# MAX78630_SOC.net
KiCad netlist of a schematic drawn in Altium Designer
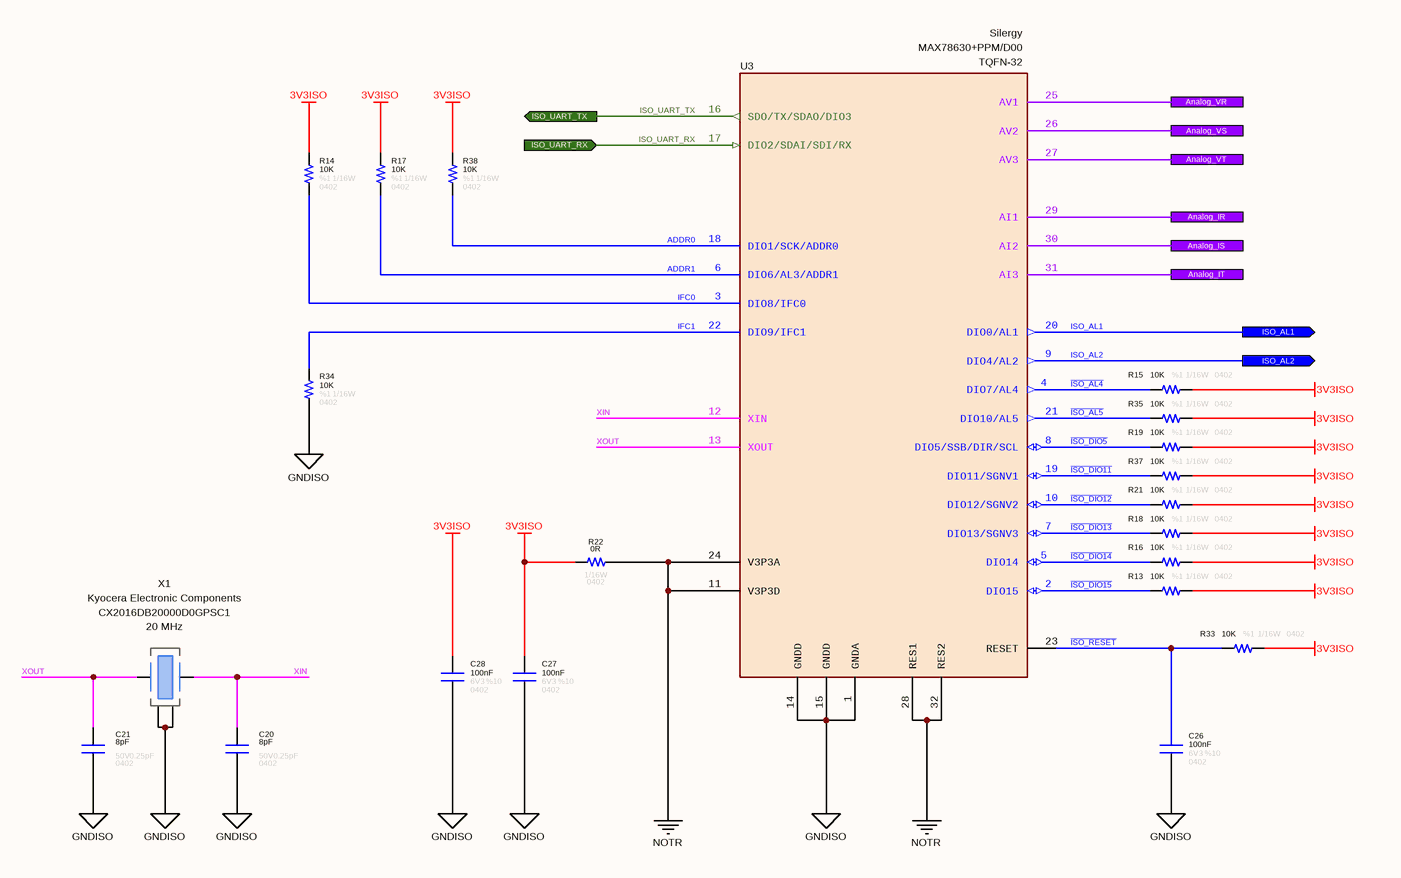
[diagram p0: MAX78630 SOC.SchDoc]

(export (version "E")
  (design (tool "Eeschema 10.0.6"))
  (components
    (comp (ref "C20")
      (value "8pF")
      (footprint "CAPACITOR_0402")
      (description "Capacitor - 8pF [0402] (Ceramic)")
      (fields
        (field (name "MANUFACTURER PART NUMBER") "04025A8R0CAT2A")
        (field (name "TOLERANCE") "0.25pF")
        (field (name "CASE") "0402")
        (field (name "VOLTAGE") "50V")
      )
      (libsource (lib "Akkoyun") (part "Capacitor - 8pF [0402-50V]"))
    )
    (comp (ref "C21")
      (value "8pF")
      (footprint "CAPACITOR_0402")
      (description "Capacitor - 8pF [0402] (Ceramic)")
      (fields
        (field (name "MANUFACTURER PART NUMBER") "04025A8R0CAT2A")
        (field (name "TOLERANCE") "0.25pF")
        (field (name "CASE") "0402")
        (field (name "VOLTAGE") "50V")
      )
      (libsource (lib "Akkoyun") (part "Capacitor - 8pF [0402-50V]"))
    )
    (comp (ref "C26")
      (value "100nF")
      (footprint "CAPACITOR_0402")
      (description "Capacitor - 100nF [0402-6V3] (Ceramic)")
      (fields
        (field (name "MANUFACTURER PART NUMBER") "04026D104KAT4A")
        (field (name "TOLERANCE") "%10")
        (field (name "VOLTAGE") "6V3")
        (field (name "CASE") "0402")
        (field (name "Comment") "Capacitor - 100nF [0402] (Ceramic)")
      )
      (libsource (lib "Akkoyun") (part "Capacitor - 100nF [0402-6V3]"))
    )
    (comp (ref "C27")
      (value "100nF")
      (footprint "CAPACITOR_0402")
      (description "Capacitor - 100nF [0402-6V3] (Ceramic)")
      (fields
        (field (name "MANUFACTURER PART NUMBER") "04026D104KAT4A")
        (field (name "TOLERANCE") "%10")
        (field (name "VOLTAGE") "6V3")
        (field (name "CASE") "0402")
        (field (name "Comment") "Capacitor - 100nF [0402] (Ceramic)")
      )
      (libsource (lib "Akkoyun") (part "Capacitor - 100nF [0402-6V3]"))
    )
    (comp (ref "C28")
      (value "100nF")
      (footprint "CAPACITOR_0402")
      (description "Capacitor - 100nF [0402-6V3] (Ceramic)")
      (fields
        (field (name "MANUFACTURER PART NUMBER") "04026D104KAT4A")
        (field (name "TOLERANCE") "%10")
        (field (name "VOLTAGE") "6V3")
        (field (name "CASE") "0402")
        (field (name "Comment") "Capacitor - 100nF [0402] (Ceramic)")
      )
      (libsource (lib "Akkoyun") (part "Capacitor - 100nF [0402-6V3]"))
    )
    (comp (ref "R13")
      (value "10K")
      (footprint "RESISTOR_0402")
      (description "Thick Film Resistors - SMD 1/16 W 10 KOhm 1%")
      (fields
        (field (name "MANUFACTURER PART NUMBER") "CRCW040210K0FKED")
        (field (name "TOLERANCE") "%1")
        (field (name "CASE") "0402")
        (field (name "POWER") "1/16W")
        (field (name "Comment") "10K - 0402 - %1 - 1/16W")
      )
      (libsource (lib "Akkoyun") (part "Resistor - 10K [0402]"))
    )
    (comp (ref "R14")
      (value "10K")
      (footprint "RESISTOR_0402")
      (description "Thick Film Resistors - SMD 1/16 W 10 KOhm 1%")
      (fields
        (field (name "MANUFACTURER PART NUMBER") "CRCW040210K0FKED")
        (field (name "TOLERANCE") "%1")
        (field (name "CASE") "0402")
        (field (name "POWER") "1/16W")
        (field (name "Comment") "10K - 0402 - %1 - 1/16W")
      )
      (libsource (lib "Akkoyun") (part "Resistor - 10K [0402]"))
    )
    (comp (ref "R15")
      (value "10K")
      (footprint "RESISTOR_0402")
      (description "Thick Film Resistors - SMD 1/16 W 10 KOhm 1%")
      (fields
        (field (name "MANUFACTURER PART NUMBER") "CRCW040210K0FKED")
        (field (name "TOLERANCE") "%1")
        (field (name "CASE") "0402")
        (field (name "POWER") "1/16W")
        (field (name "Comment") "10K - 0402 - %1 - 1/16W")
      )
      (libsource (lib "Akkoyun") (part "Resistor - 10K [0402]"))
    )
    (comp (ref "R16")
      (value "10K")
      (footprint "RESISTOR_0402")
      (description "Thick Film Resistors - SMD 1/16 W 10 KOhm 1%")
      (fields
        (field (name "MANUFACTURER PART NUMBER") "CRCW040210K0FKED")
        (field (name "TOLERANCE") "%1")
        (field (name "CASE") "0402")
        (field (name "POWER") "1/16W")
        (field (name "Comment") "10K - 0402 - %1 - 1/16W")
      )
      (libsource (lib "Akkoyun") (part "Resistor - 10K [0402]"))
    )
    (comp (ref "R17")
      (value "10K")
      (footprint "RESISTOR_0402")
      (description "Thick Film Resistors - SMD 1/16 W 10 KOhm 1%")
      (fields
        (field (name "MANUFACTURER PART NUMBER") "CRCW040210K0FKED")
        (field (name "TOLERANCE") "%1")
        (field (name "CASE") "0402")
        (field (name "POWER") "1/16W")
        (field (name "Comment") "10K - 0402 - %1 - 1/16W")
      )
      (libsource (lib "Akkoyun") (part "Resistor - 10K [0402]"))
    )
    (comp (ref "R18")
      (value "10K")
      (footprint "RESISTOR_0402")
      (description "Thick Film Resistors - SMD 1/16 W 10 KOhm 1%")
      (fields
        (field (name "MANUFACTURER PART NUMBER") "CRCW040210K0FKED")
        (field (name "TOLERANCE") "%1")
        (field (name "CASE") "0402")
        (field (name "POWER") "1/16W")
        (field (name "Comment") "10K - 0402 - %1 - 1/16W")
      )
      (libsource (lib "Akkoyun") (part "Resistor - 10K [0402]"))
    )
    (comp (ref "R19")
      (value "10K")
      (footprint "RESISTOR_0402")
      (description "Thick Film Resistors - SMD 1/16 W 10 KOhm 1%")
      (fields
        (field (name "MANUFACTURER PART NUMBER") "CRCW040210K0FKED")
        (field (name "TOLERANCE") "%1")
        (field (name "CASE") "0402")
        (field (name "POWER") "1/16W")
        (field (name "Comment") "10K - 0402 - %1 - 1/16W")
      )
      (libsource (lib "Akkoyun") (part "Resistor - 10K [0402]"))
    )
    (comp (ref "R21")
      (value "10K")
      (footprint "RESISTOR_0402")
      (description "Thick Film Resistors - SMD 1/16 W 10 KOhm 1%")
      (fields
        (field (name "MANUFACTURER PART NUMBER") "CRCW040210K0FKED")
        (field (name "TOLERANCE") "%1")
        (field (name "CASE") "0402")
        (field (name "POWER") "1/16W")
        (field (name "Comment") "10K - 0402 - %1 - 1/16W")
      )
      (libsource (lib "Akkoyun") (part "Resistor - 10K [0402]"))
    )
    (comp (ref "R22")
      (value "0R")
      (footprint "RESISTOR_0402")
      (description "Thick Film Resistors - SMD 1/16 W 0 Ohm")
      (fields
        (field (name "MANUFACTURER PART NUMBER") "CRCW04020000Z0ED")
        (field (name "CASE") "0402")
        (field (name "POWER") "1/16W")
        (field (name "Comment") "0R - 0402 - %1 - 1/16W")
      )
      (libsource (lib "Akkoyun") (part "Resistor - 0R [0402]"))
    )
    (comp (ref "R33")
      (value "10K")
      (footprint "RESISTOR_0402")
      (description "Thick Film Resistors - SMD 1/16 W 10 KOhm 1%")
      (fields
        (field (name "MANUFACTURER PART NUMBER") "CRCW040210K0FKED")
        (field (name "TOLERANCE") "%1")
        (field (name "CASE") "0402")
        (field (name "POWER") "1/16W")
        (field (name "Comment") "10K - 0402 - %1 - 1/16W")
      )
      (libsource (lib "Akkoyun") (part "Resistor - 10K [0402]"))
    )
    (comp (ref "R34")
      (value "10K")
      (footprint "RESISTOR_0402")
      (description "Thick Film Resistors - SMD 1/16 W 10 KOhm 1%")
      (fields
        (field (name "MANUFACTURER PART NUMBER") "CRCW040210K0FKED")
        (field (name "TOLERANCE") "%1")
        (field (name "CASE") "0402")
        (field (name "POWER") "1/16W")
        (field (name "Comment") "10K - 0402 - %1 - 1/16W")
      )
      (libsource (lib "Akkoyun") (part "Resistor - 10K [0402]"))
    )
    (comp (ref "R35")
      (value "10K")
      (footprint "RESISTOR_0402")
      (description "Thick Film Resistors - SMD 1/16 W 10 KOhm 1%")
      (fields
        (field (name "MANUFACTURER PART NUMBER") "CRCW040210K0FKED")
        (field (name "TOLERANCE") "%1")
        (field (name "CASE") "0402")
        (field (name "POWER") "1/16W")
        (field (name "Comment") "10K - 0402 - %1 - 1/16W")
      )
      (libsource (lib "Akkoyun") (part "Resistor - 10K [0402]"))
    )
    (comp (ref "R37")
      (value "10K")
      (footprint "RESISTOR_0402")
      (description "Thick Film Resistors - SMD 1/16 W 10 KOhm 1%")
      (fields
        (field (name "MANUFACTURER PART NUMBER") "CRCW040210K0FKED")
        (field (name "TOLERANCE") "%1")
        (field (name "CASE") "0402")
        (field (name "POWER") "1/16W")
        (field (name "Comment") "10K - 0402 - %1 - 1/16W")
      )
      (libsource (lib "Akkoyun") (part "Resistor - 10K [0402]"))
    )
    (comp (ref "R38")
      (value "10K")
      (footprint "RESISTOR_0402")
      (description "Thick Film Resistors - SMD 1/16 W 10 KOhm 1%")
      (fields
        (field (name "MANUFACTURER PART NUMBER") "CRCW040210K0FKED")
        (field (name "TOLERANCE") "%1")
        (field (name "CASE") "0402")
        (field (name "POWER") "1/16W")
        (field (name "Comment") "10K - 0402 - %1 - 1/16W")
      )
      (libsource (lib "Akkoyun") (part "Resistor - 10K [0402]"))
    )
    (comp (ref "U3")
      (value "MAX78630+PPM/D00")
      (footprint "TQFN-32 - Maxim")
      (description "Energy Measurement Processor 32-Pin TQFN EP Tube")
      (fields
        (field (name "MANUFACTURER NAME") "Silergy")
        (field (name "MANUFACTURER PART NUMBER") "MAX78630+PPM/D00")
        (field (name "CASE") "TQFN-32")
      )
      (libsource (lib "Akkoyun") (part "IC - MAX78630"))
    )
    (comp (ref "X1")
      (value "CX2016DB20000D0GPSC1")
      (footprint "CRYSTAL - 20MHz")
      (description "Crystals AEC-Q200 20000kHz 8pF 2x1.6mm")
      (fields
        (field (name "MANUFACTURER NAME") "Kyocera Electronic Components")
        (field (name "MANUFACTURER PART NUMBER") "CX2016DB20000D0GPSC1")
        (field (name "FREQUENCY") "20 MHz")
      )
      (libsource (lib "Akkoyun") (part "Crystal - 20MHz"))
    )
  )
  (nets
    (net (code "1") (name "/ADDR0") (class "Default")
      (node (ref "R38") (pin "1") (pinfunction "1_1") (pintype "passive"))
      (node (ref "U3") (pin "18") (pinfunction "DIO1/SCK/ADDR0_18") (pintype "passive"))
    )
    (net (code "2") (name "/ADDR1") (class "Default")
      (node (ref "R17") (pin "1") (pinfunction "1_1") (pintype "passive"))
      (node (ref "U3") (pin "6") (pinfunction "DIO6/AL3/ADDR1_6") (pintype "passive"))
    )
    (net (code "3") (name "/Analog_IR") (class "Default")
      (node (ref "U3") (pin "29") (pinfunction "AI1_29") (pintype "passive"))
    )
    (net (code "4") (name "/Analog_IS") (class "Default")
      (node (ref "U3") (pin "30") (pinfunction "AI2_30") (pintype "passive"))
    )
    (net (code "5") (name "/Analog_IT") (class "Default")
      (node (ref "U3") (pin "31") (pinfunction "AI3_31") (pintype "passive"))
    )
    (net (code "6") (name "/Analog_VR") (class "Default")
      (node (ref "U3") (pin "25") (pinfunction "AV1_25") (pintype "passive"))
    )
    (net (code "7") (name "/Analog_VS") (class "Default")
      (node (ref "U3") (pin "26") (pinfunction "AV2_26") (pintype "passive"))
    )
    (net (code "8") (name "/Analog_VT") (class "Default")
      (node (ref "U3") (pin "27") (pinfunction "AV3_27") (pintype "passive"))
    )
    (net (code "9") (name "/IFC0") (class "Default")
      (node (ref "R14") (pin "1") (pinfunction "1_1") (pintype "passive"))
      (node (ref "U3") (pin "3") (pinfunction "DIO8/IFC0_3") (pintype "passive"))
    )
    (net (code "10") (name "/IFC1") (class "Default")
      (node (ref "R34") (pin "2") (pinfunction "2_2") (pintype "passive"))
      (node (ref "U3") (pin "22") (pinfunction "DIO9/IFC1_22") (pintype "passive"))
    )
    (net (code "11") (name "/ISO_AL1") (class "Default")
      (node (ref "U3") (pin "20") (pinfunction "DIO0/AL1_20") (pintype "output"))
    )
    (net (code "12") (name "/ISO_AL2") (class "Default")
      (node (ref "U3") (pin "9") (pinfunction "DIO4/AL2_9") (pintype "output"))
    )
    (net (code "13") (name "/ISO_UART_RX") (class "Default")
      (node (ref "U3") (pin "17") (pinfunction "DIO2/SDAI/SDI/RX_17") (pintype "input"))
    )
    (net (code "14") (name "/ISO_UART_TX") (class "Default")
      (node (ref "U3") (pin "16") (pinfunction "SDO/TX/SDAO/DIO3_16") (pintype "output"))
    )
    (net (code "15") (name "/XIN") (class "Default")
      (node (ref "C20") (pin "2") (pinfunction "2_2") (pintype "passive"))
      (node (ref "U3") (pin "12") (pinfunction "XIN_12") (pintype "passive"))
      (node (ref "X1") (pin "1") (pinfunction "IN/OUT_1") (pintype "passive"))
    )
    (net (code "16") (name "/XOUT") (class "Default")
      (node (ref "C21") (pin "2") (pinfunction "2_2") (pintype "passive"))
      (node (ref "U3") (pin "13") (pinfunction "XOUT_13") (pintype "passive"))
      (node (ref "X1") (pin "3") (pinfunction "OUT/IN_3") (pintype "passive"))
    )
    (net (code "17") (name "/~{ISO_AL4}") (class "Default")
      (node (ref "R15") (pin "2") (pinfunction "2_2") (pintype "passive"))
      (node (ref "U3") (pin "4") (pinfunction "DIO7/AL4_4") (pintype "output"))
    )
    (net (code "18") (name "/~{ISO_AL5}") (class "Default")
      (node (ref "R35") (pin "2") (pinfunction "2_2") (pintype "passive"))
      (node (ref "U3") (pin "21") (pinfunction "DIO10/AL5_21") (pintype "output"))
    )
    (net (code "19") (name "/~{ISO_DIO5}") (class "Default")
      (node (ref "R19") (pin "2") (pinfunction "2_2") (pintype "passive"))
      (node (ref "U3") (pin "8") (pinfunction "DIO5/SSB/DIR/SCL_8") (pintype "bidirectional"))
    )
    (net (code "20") (name "/~{ISO_DIO11}") (class "Default")
      (node (ref "R37") (pin "2") (pinfunction "2_2") (pintype "passive"))
      (node (ref "U3") (pin "19") (pinfunction "DIO11/SGNV1_19") (pintype "bidirectional"))
    )
    (net (code "21") (name "/~{ISO_DIO12}") (class "Default")
      (node (ref "R21") (pin "2") (pinfunction "2_2") (pintype "passive"))
      (node (ref "U3") (pin "10") (pinfunction "DIO12/SGNV2_10") (pintype "bidirectional"))
    )
    (net (code "22") (name "/~{ISO_DIO13}") (class "Default")
      (node (ref "R18") (pin "2") (pinfunction "2_2") (pintype "passive"))
      (node (ref "U3") (pin "7") (pinfunction "DIO13/SGNV3_7") (pintype "bidirectional"))
    )
    (net (code "23") (name "/~{ISO_DIO14}") (class "Default")
      (node (ref "R16") (pin "2") (pinfunction "2_2") (pintype "passive"))
      (node (ref "U3") (pin "5") (pinfunction "DIO14_5") (pintype "bidirectional"))
    )
    (net (code "24") (name "/~{ISO_DIO15}") (class "Default")
      (node (ref "R13") (pin "2") (pinfunction "2_2") (pintype "passive"))
      (node (ref "U3") (pin "2") (pinfunction "DIO15_2") (pintype "bidirectional"))
    )
    (net (code "25") (name "/~{ISO_RESET}") (class "Default")
      (node (ref "C26") (pin "2") (pinfunction "2_2") (pintype "passive"))
      (node (ref "R33") (pin "2") (pinfunction "2_2") (pintype "passive"))
      (node (ref "U3") (pin "23") (pinfunction "RESET_23") (pintype "open_collector"))
    )
    (net (code "26") (name "3V3ISO") (class "Default")
      (node (ref "C27") (pin "2") (pinfunction "2_2") (pintype "passive"))
      (node (ref "C28") (pin "2") (pinfunction "2_2") (pintype "passive"))
      (node (ref "R13") (pin "1") (pinfunction "1_1") (pintype "passive"))
      (node (ref "R14") (pin "2") (pinfunction "2_2") (pintype "passive"))
      (node (ref "R15") (pin "1") (pinfunction "1_1") (pintype "passive"))
      (node (ref "R16") (pin "1") (pinfunction "1_1") (pintype "passive"))
      (node (ref "R17") (pin "2") (pinfunction "2_2") (pintype "passive"))
      (node (ref "R18") (pin "1") (pinfunction "1_1") (pintype "passive"))
      (node (ref "R19") (pin "1") (pinfunction "1_1") (pintype "passive"))
      (node (ref "R21") (pin "1") (pinfunction "1_1") (pintype "passive"))
      (node (ref "R22") (pin "2") (pinfunction "2_2") (pintype "passive"))
      (node (ref "R33") (pin "1") (pinfunction "1_1") (pintype "passive"))
      (node (ref "R35") (pin "1") (pinfunction "1_1") (pintype "passive"))
      (node (ref "R37") (pin "1") (pinfunction "1_1") (pintype "passive"))
      (node (ref "R38") (pin "2") (pinfunction "2_2") (pintype "passive"))
    )
    (net (code "27") (name "GNDISO") (class "Default")
      (node (ref "C20") (pin "1") (pinfunction "1_1") (pintype "passive"))
      (node (ref "C21") (pin "1") (pinfunction "1_1") (pintype "passive"))
      (node (ref "C26") (pin "1") (pinfunction "1_1") (pintype "passive"))
      (node (ref "C27") (pin "1") (pinfunction "1_1") (pintype "passive"))
      (node (ref "C28") (pin "1") (pinfunction "1_1") (pintype "passive"))
      (node (ref "R34") (pin "1") (pinfunction "1_1") (pintype "passive"))
      (node (ref "U3") (pin "1") (pinfunction "GNDA_1") (pintype "power_in"))
      (node (ref "U3") (pin "14") (pinfunction "GNDD_14") (pintype "power_in"))
      (node (ref "U3") (pin "15") (pinfunction "GNDD_15") (pintype "power_in"))
      (node (ref "X1") (pin "2") (pinfunction "GND_2") (pintype "passive"))
      (node (ref "X1") (pin "4") (pinfunction "GND_4") (pintype "passive"))
    )
    (net (code "28") (name "NOTR") (class "Default")
      (node (ref "R22") (pin "1") (pinfunction "1_1") (pintype "passive"))
      (node (ref "U3") (pin "11") (pinfunction "V3P3D_11") (pintype "power_in"))
      (node (ref "U3") (pin "24") (pinfunction "V3P3A_24") (pintype "power_in"))
      (node (ref "U3") (pin "28") (pinfunction "RES1_28") (pintype "passive"))
      (node (ref "U3") (pin "32") (pinfunction "RES2_32") (pintype "passive"))
    )
  )
)
